# afron_atmega328_chassis_SMD.net
KiCad netlist of a schematic drawn in EAGLE
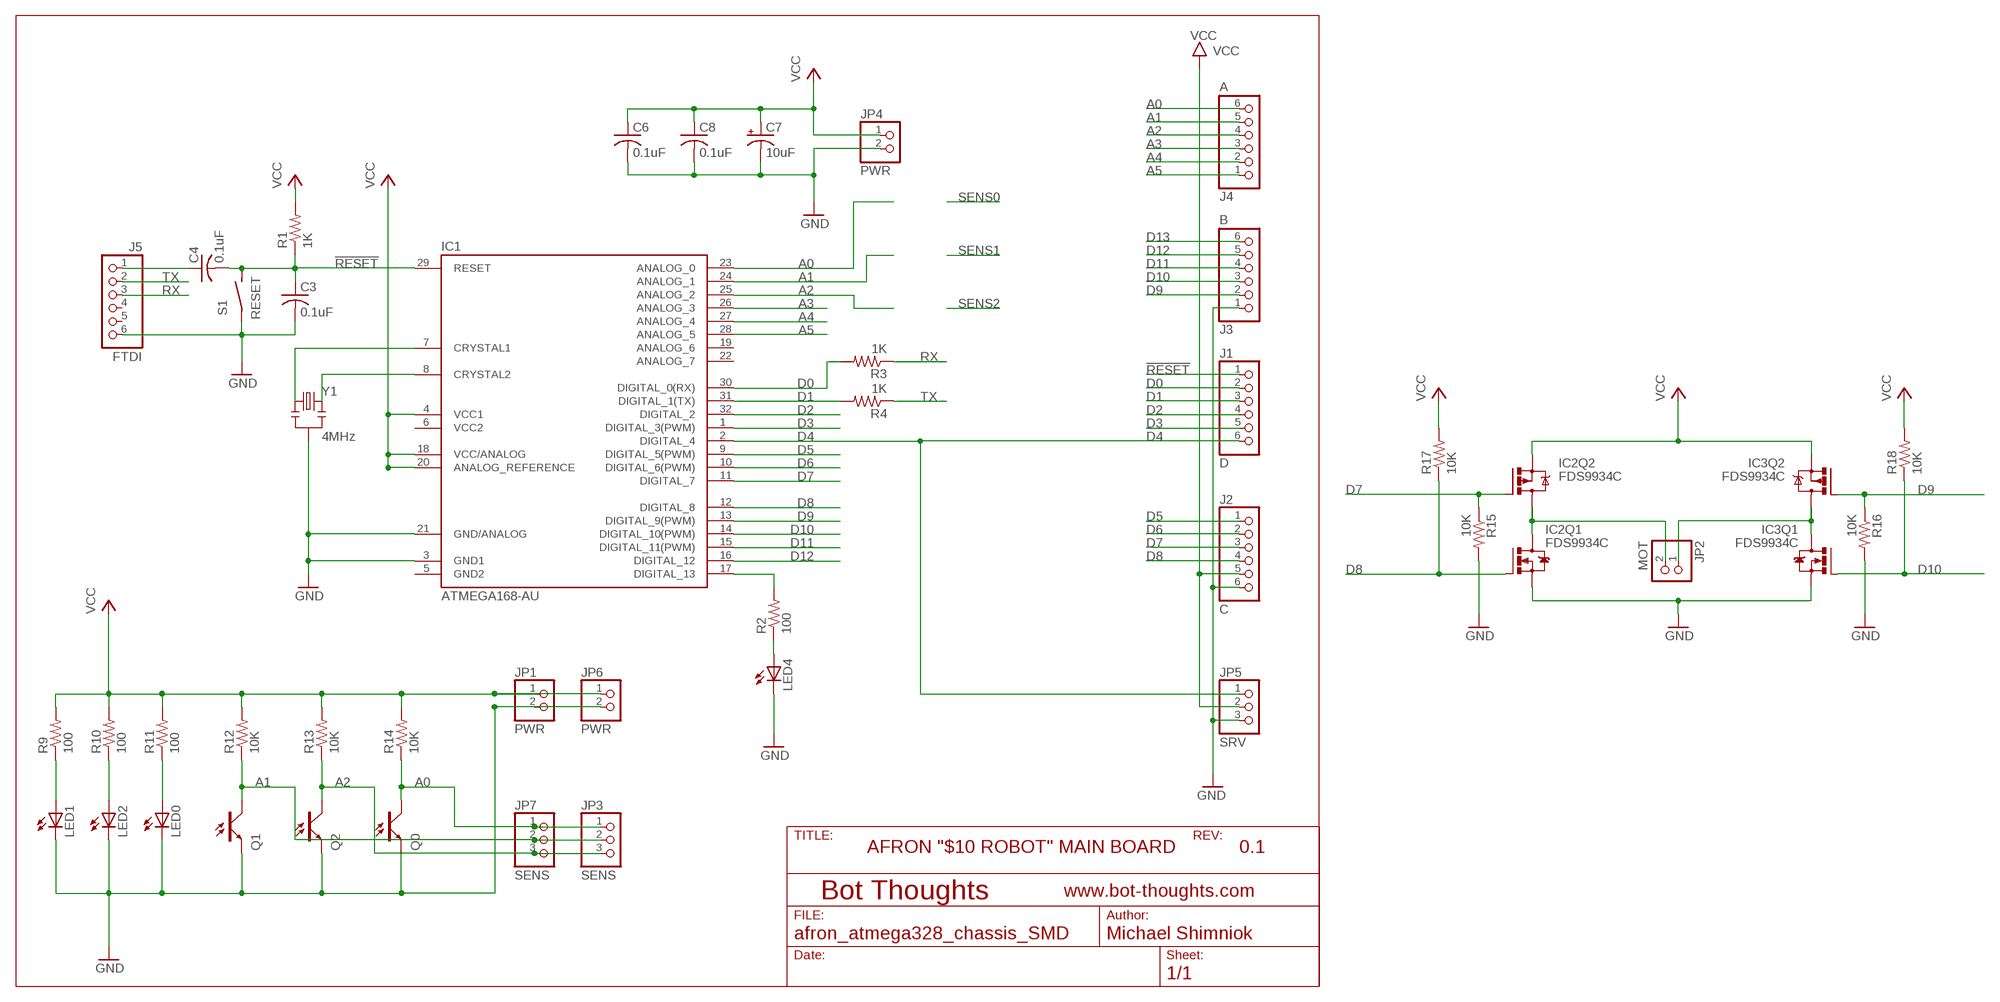
[diagram p0: schematic, sheet 1]

(export (version "E")
  (design (tool "Eeschema 10.0.6"))
  (components
    (comp (ref "C3")
      (value "0.1uF")
      (footprint "eagle-import:C0603")
      (libsource (lib "eagle-import") (part "C-USC0603"))
    )
    (comp (ref "C4")
      (value "0.1uF")
      (footprint "eagle-import:C0603")
      (libsource (lib "eagle-import") (part "C-USC0603"))
    )
    (comp (ref "C6")
      (value "0.1uF")
      (footprint "eagle-import:C0603")
      (libsource (lib "eagle-import") (part "C-USC0603"))
    )
    (comp (ref "C7")
      (value "10uF")
      (footprint "eagle-import:E2,5-6")
      (libsource (lib "eagle-import") (part "CPOL-USE2.5-6"))
    )
    (comp (ref "C8")
      (value "0.1uF")
      (footprint "eagle-import:C0603")
      (libsource (lib "eagle-import") (part "C-USC0603"))
    )
    (comp (ref "IC1")
      (value "ATMEGA168-AU")
      (footprint "eagle-import:TQFP32-08")
      (libsource (lib "eagle-import") (part "ATMEGA168-AU"))
    )
    (comp (ref "IC2")
      (value "FDS9934C")
      (footprint "eagle-import:SOIC8")
      (libsource (lib "eagle-import") (part "FDS9934C"))
    )
    (comp (ref "IC3")
      (value "FDS9934C")
      (footprint "eagle-import:SOIC8")
      (libsource (lib "eagle-import") (part "FDS9934C"))
    )
    (comp (ref "J1")
      (value "D")
      (footprint "eagle-import:1X06-S")
      (libsource (lib "eagle-import") (part "PINHD-1X06_2.54-S"))
    )
    (comp (ref "J2")
      (value "C")
      (footprint "eagle-import:1X06-S")
      (libsource (lib "eagle-import") (part "PINHD-1X06_2.54-S"))
    )
    (comp (ref "J3")
      (value "B")
      (footprint "eagle-import:1X06-S")
      (libsource (lib "eagle-import") (part "PINHD-1X06_2.54-S"))
    )
    (comp (ref "J4")
      (value "A")
      (footprint "eagle-import:1X06-S")
      (libsource (lib "eagle-import") (part "PINHD-1X06_2.54-S"))
    )
    (comp (ref "J5")
      (value "FTDI")
      (footprint "eagle-import:1X06-S")
      (libsource (lib "eagle-import") (part "PINHD-1X06_2.54-S"))
    )
    (comp (ref "JP1")
      (value "PWR")
      (footprint "eagle-import:1X02-S")
      (libsource (lib "eagle-import") (part "PINHD-1X02_2.54-S"))
    )
    (comp (ref "JP2")
      (value "MOT")
      (footprint "eagle-import:1X02-S")
      (libsource (lib "eagle-import") (part "PINHD-1X02_2.54-S"))
    )
    (comp (ref "JP3")
      (value "SENS")
      (footprint "eagle-import:1X03-S")
      (libsource (lib "eagle-import") (part "PINHD-1X03_2.54-S"))
    )
    (comp (ref "JP4")
      (value "PWR")
      (footprint "eagle-import:1X02-S")
      (libsource (lib "eagle-import") (part "PINHD-1X02_2.54-S"))
    )
    (comp (ref "JP5")
      (value "SRV")
      (footprint "eagle-import:1X03-S")
      (libsource (lib "eagle-import") (part "PINHD-1X03_2.54-S"))
    )
    (comp (ref "JP6")
      (value "PWR")
      (footprint "eagle-import:1X02-S")
      (libsource (lib "eagle-import") (part "PINHD-1X02_2.54-S"))
    )
    (comp (ref "JP7")
      (value "SENS")
      (footprint "eagle-import:1X03-S")
      (libsource (lib "eagle-import") (part "PINHD-1X03_2.54-S"))
    )
    (comp (ref "LED0")
      (value "LED3MM")
      (footprint "eagle-import:LED3MM")
      (libsource (lib "eagle-import") (part "LED3MM"))
    )
    (comp (ref "LED1")
      (value "LED3MM")
      (footprint "eagle-import:LED3MM")
      (libsource (lib "eagle-import") (part "LED3MM"))
    )
    (comp (ref "LED2")
      (value "LED3MM")
      (footprint "eagle-import:LED3MM")
      (libsource (lib "eagle-import") (part "LED3MM"))
    )
    (comp (ref "LED4")
      (value "LEDCHIP-LED0603")
      (footprint "eagle-import:CHIP-LED0603")
      (libsource (lib "eagle-import") (part "LEDCHIP-LED0603"))
    )
    (comp (ref "Q0")
      (value "PHOTOTRANSISTOR3MM")
      (footprint "eagle-import:LED3MM")
      (libsource (lib "eagle-import") (part "PHOTOTRANSISTOR3MM"))
    )
    (comp (ref "Q1")
      (value "PHOTOTRANSISTOR3MM")
      (footprint "eagle-import:LED3MM")
      (libsource (lib "eagle-import") (part "PHOTOTRANSISTOR3MM"))
    )
    (comp (ref "Q2")
      (value "PHOTOTRANSISTOR3MM")
      (footprint "eagle-import:LED3MM")
      (libsource (lib "eagle-import") (part "PHOTOTRANSISTOR3MM"))
    )
    (comp (ref "R1")
      (value "1K")
      (footprint "eagle-import:R0603")
      (libsource (lib "eagle-import") (part "R-US_R0603"))
    )
    (comp (ref "R2")
      (value "100")
      (footprint "eagle-import:R0603")
      (libsource (lib "eagle-import") (part "R-US_R0603"))
    )
    (comp (ref "R3")
      (value "1K")
      (footprint "eagle-import:R0603")
      (libsource (lib "eagle-import") (part "R-US_R0603"))
    )
    (comp (ref "R4")
      (value "1K")
      (footprint "eagle-import:R0603")
      (libsource (lib "eagle-import") (part "R-US_R0603"))
    )
    (comp (ref "R9")
      (value "100")
      (footprint "eagle-import:R0603")
      (libsource (lib "eagle-import") (part "R-US_R0603"))
    )
    (comp (ref "R10")
      (value "100")
      (footprint "eagle-import:R0603")
      (libsource (lib "eagle-import") (part "R-US_R0603"))
    )
    (comp (ref "R11")
      (value "100")
      (footprint "eagle-import:R0603")
      (libsource (lib "eagle-import") (part "R-US_R0603"))
    )
    (comp (ref "R12")
      (value "10K")
      (footprint "eagle-import:R0603")
      (libsource (lib "eagle-import") (part "R-US_R0603"))
    )
    (comp (ref "R13")
      (value "10K")
      (footprint "eagle-import:R0603")
      (libsource (lib "eagle-import") (part "R-US_R0603"))
    )
    (comp (ref "R14")
      (value "10K")
      (footprint "eagle-import:R0603")
      (libsource (lib "eagle-import") (part "R-US_R0603"))
    )
    (comp (ref "R15")
      (value "10K")
      (footprint "eagle-import:R0603")
      (libsource (lib "eagle-import") (part "R-US_R0603"))
    )
    (comp (ref "R16")
      (value "10K")
      (footprint "eagle-import:R0603")
      (libsource (lib "eagle-import") (part "R-US_R0603"))
    )
    (comp (ref "R17")
      (value "10K")
      (footprint "eagle-import:R0603")
      (libsource (lib "eagle-import") (part "R-US_R0603"))
    )
    (comp (ref "R18")
      (value "10K")
      (footprint "eagle-import:R0603")
      (libsource (lib "eagle-import") (part "R-US_R0603"))
    )
    (comp (ref "S1")
      (value "RESET")
      (footprint "eagle-import:6MMTACTTILE_RECT_SMD")
      (libsource (lib "eagle-import") (part "SPST_TACT_RECT_SMD"))
    )
    (comp (ref "Y1")
      (value "4MHz")
      (footprint "eagle-import:RESONATOR-SMD")
      (libsource (lib "eagle-import") (part "RESONATORSMD"))
    )
  )
  (nets
    (net (code "1") (name "/A0") (class "Default")
      (node (ref "IC1") (pin "23") (pinfunction "ANALOG_0_23") (pintype "bidirectional"))
      (node (ref "J4") (pin "6") (pinfunction "6_6") (pintype "passive"))
      (node (ref "JP3") (pin "1") (pinfunction "1_1") (pintype "passive"))
      (node (ref "JP7") (pin "1") (pinfunction "1_1") (pintype "passive"))
      (node (ref "Q0") (pin "A") (pinfunction "A_A") (pintype "passive"))
      (node (ref "R14") (pin "1") (pinfunction "1_1") (pintype "passive"))
    )
    (net (code "2") (name "/A1") (class "Default")
      (node (ref "IC1") (pin "24") (pinfunction "ANALOG_1_24") (pintype "bidirectional"))
      (node (ref "J4") (pin "5") (pinfunction "5_5") (pintype "passive"))
      (node (ref "JP3") (pin "2") (pinfunction "2_2") (pintype "passive"))
      (node (ref "JP7") (pin "2") (pinfunction "2_2") (pintype "passive"))
      (node (ref "Q1") (pin "A") (pinfunction "A_A") (pintype "passive"))
      (node (ref "R12") (pin "1") (pinfunction "1_1") (pintype "passive"))
    )
    (net (code "3") (name "/A2") (class "Default")
      (node (ref "IC1") (pin "25") (pinfunction "ANALOG_2_25") (pintype "bidirectional"))
      (node (ref "J4") (pin "4") (pinfunction "4_4") (pintype "passive"))
      (node (ref "JP3") (pin "3") (pinfunction "3_3") (pintype "passive"))
      (node (ref "JP7") (pin "3") (pinfunction "3_3") (pintype "passive"))
      (node (ref "Q2") (pin "A") (pinfunction "A_A") (pintype "passive"))
      (node (ref "R13") (pin "1") (pinfunction "1_1") (pintype "passive"))
    )
    (net (code "4") (name "/A3") (class "Default")
      (node (ref "IC1") (pin "26") (pinfunction "ANALOG_3_26") (pintype "bidirectional"))
      (node (ref "J4") (pin "3") (pinfunction "3_3") (pintype "passive"))
    )
    (net (code "5") (name "/A4") (class "Default")
      (node (ref "IC1") (pin "27") (pinfunction "ANALOG_4_27") (pintype "bidirectional"))
      (node (ref "J4") (pin "2") (pinfunction "2_2") (pintype "passive"))
    )
    (net (code "6") (name "/A5") (class "Default")
      (node (ref "IC1") (pin "28") (pinfunction "ANALOG_5_28") (pintype "bidirectional"))
      (node (ref "J4") (pin "1") (pinfunction "1_1") (pintype "passive"))
    )
    (net (code "7") (name "/D0") (class "Default")
      (node (ref "IC1") (pin "30") (pinfunction "DIGITAL_0(RX)_30") (pintype "bidirectional"))
      (node (ref "J1") (pin "2") (pinfunction "2_2") (pintype "passive"))
      (node (ref "R3") (pin "2") (pinfunction "2_2") (pintype "passive"))
    )
    (net (code "8") (name "/D1") (class "Default")
      (node (ref "IC1") (pin "31") (pinfunction "DIGITAL_1(TX)_31") (pintype "bidirectional"))
      (node (ref "J1") (pin "3") (pinfunction "3_3") (pintype "passive"))
      (node (ref "R4") (pin "2") (pinfunction "2_2") (pintype "passive"))
    )
    (net (code "9") (name "/D2") (class "Default")
      (node (ref "IC1") (pin "32") (pinfunction "DIGITAL_2_32") (pintype "bidirectional"))
      (node (ref "J1") (pin "4") (pinfunction "4_4") (pintype "passive"))
    )
    (net (code "10") (name "/D3") (class "Default")
      (node (ref "IC1") (pin "1") (pinfunction "DIGITAL_3(PWM)_1") (pintype "bidirectional"))
      (node (ref "J1") (pin "5") (pinfunction "5_5") (pintype "passive"))
    )
    (net (code "11") (name "/D4") (class "Default")
      (node (ref "IC1") (pin "2") (pinfunction "DIGITAL_4_2") (pintype "bidirectional"))
      (node (ref "J1") (pin "6") (pinfunction "6_6") (pintype "passive"))
      (node (ref "JP5") (pin "1") (pinfunction "1_1") (pintype "passive"))
    )
    (net (code "12") (name "/D5") (class "Default")
      (node (ref "IC1") (pin "9") (pinfunction "DIGITAL_5(PWM)_9") (pintype "bidirectional"))
      (node (ref "J2") (pin "1") (pinfunction "1_1") (pintype "passive"))
    )
    (net (code "13") (name "/D6") (class "Default")
      (node (ref "IC1") (pin "10") (pinfunction "DIGITAL_6(PWM)_10") (pintype "bidirectional"))
      (node (ref "J2") (pin "2") (pinfunction "2_2") (pintype "passive"))
    )
    (net (code "14") (name "/D7") (class "Default")
      (node (ref "IC1") (pin "11") (pinfunction "DIGITAL_7_11") (pintype "bidirectional"))
      (node (ref "IC2") (pin "4") (pinfunction "G_4") (pintype "passive"))
      (node (ref "J2") (pin "3") (pinfunction "3_3") (pintype "passive"))
      (node (ref "R15") (pin "1") (pinfunction "1_1") (pintype "passive"))
    )
    (net (code "15") (name "/D8") (class "Default")
      (node (ref "IC1") (pin "12") (pinfunction "DIGITAL_8_12") (pintype "bidirectional"))
      (node (ref "IC2") (pin "2") (pinfunction "G_2") (pintype "passive"))
      (node (ref "J2") (pin "4") (pinfunction "4_4") (pintype "passive"))
      (node (ref "R17") (pin "1") (pinfunction "1_1") (pintype "passive"))
    )
    (net (code "16") (name "/D9") (class "Default")
      (node (ref "IC1") (pin "13") (pinfunction "DIGITAL_9(PWM)_13") (pintype "bidirectional"))
      (node (ref "IC3") (pin "4") (pinfunction "G_4") (pintype "passive"))
      (node (ref "J3") (pin "2") (pinfunction "2_2") (pintype "passive"))
      (node (ref "R16") (pin "1") (pinfunction "1_1") (pintype "passive"))
    )
    (net (code "17") (name "/D10") (class "Default")
      (node (ref "IC1") (pin "14") (pinfunction "DIGITAL_10(PWM)_14") (pintype "bidirectional"))
      (node (ref "IC3") (pin "2") (pinfunction "G_2") (pintype "passive"))
      (node (ref "J3") (pin "3") (pinfunction "3_3") (pintype "passive"))
      (node (ref "R18") (pin "1") (pinfunction "1_1") (pintype "passive"))
    )
    (net (code "18") (name "/D11") (class "Default")
      (node (ref "IC1") (pin "15") (pinfunction "DIGITAL_11(PWM)_15") (pintype "bidirectional"))
      (node (ref "J3") (pin "4") (pinfunction "4_4") (pintype "passive"))
    )
    (net (code "19") (name "/D12") (class "Default")
      (node (ref "IC1") (pin "16") (pinfunction "DIGITAL_12_16") (pintype "bidirectional"))
      (node (ref "J3") (pin "5") (pinfunction "5_5") (pintype "passive"))
    )
    (net (code "20") (name "/D13") (class "Default")
      (node (ref "IC1") (pin "17") (pinfunction "DIGITAL_13_17") (pintype "bidirectional"))
      (node (ref "J3") (pin "6") (pinfunction "6_6") (pintype "passive"))
      (node (ref "R2") (pin "2") (pinfunction "2_2") (pintype "passive"))
    )
    (net (code "21") (name "/GND2") (class "Default")
      (node (ref "IC1") (pin "5") (pinfunction "GND2_5") (pintype "power_in"))
    )
    (net (code "22") (name "/RX") (class "Default")
      (node (ref "J5") (pin "3") (pinfunction "3_3") (pintype "passive"))
      (node (ref "R3") (pin "1") (pinfunction "1_1") (pintype "passive"))
    )
    (net (code "26") (name "/TX") (class "Default")
      (node (ref "J5") (pin "2") (pinfunction "2_2") (pintype "passive"))
      (node (ref "R4") (pin "1") (pinfunction "1_1") (pintype "passive"))
    )
    (net (code "27") (name "/VCC2") (class "Default")
      (node (ref "IC1") (pin "6") (pinfunction "VCC2_6") (pintype "power_in"))
    )
    (net (code "28") (name "/~{RESET}") (class "Default")
      (node (ref "C3") (pin "1") (pinfunction "1_1") (pintype "passive"))
      (node (ref "C4") (pin "2") (pinfunction "2_2") (pintype "passive"))
      (node (ref "IC1") (pin "29") (pinfunction "RESET_29") (pintype "bidirectional"))
      (node (ref "J1") (pin "1") (pinfunction "1_1") (pintype "passive"))
      (node (ref "R1") (pin "1") (pinfunction "1_1") (pintype "passive"))
      (node (ref "S1") (pin "P$2") (pinfunction "S_P$2") (pintype "passive"))
    )
    (net (code "29") (name "GND") (class "Default")
      (node (ref "C3") (pin "2") (pinfunction "2_2") (pintype "passive"))
      (node (ref "C6") (pin "2") (pinfunction "2_2") (pintype "passive"))
      (node (ref "C7") (pin "-") (pinfunction "-_-") (pintype "passive"))
      (node (ref "C8") (pin "2") (pinfunction "2_2") (pintype "passive"))
      (node (ref "IC1") (pin "21") (pinfunction "GND/ANALOG_21") (pintype "power_in"))
      (node (ref "IC1") (pin "3") (pinfunction "GND1_3") (pintype "power_in"))
      (node (ref "IC2") (pin "1") (pinfunction "S_1") (pintype "passive"))
      (node (ref "IC3") (pin "1") (pinfunction "S_1") (pintype "passive"))
      (node (ref "J2") (pin "6") (pinfunction "6_6") (pintype "passive"))
      (node (ref "J3") (pin "1") (pinfunction "1_1") (pintype "passive"))
      (node (ref "J5") (pin "6") (pinfunction "6_6") (pintype "passive"))
      (node (ref "JP1") (pin "2") (pinfunction "2_2") (pintype "passive"))
      (node (ref "JP4") (pin "2") (pinfunction "2_2") (pintype "passive"))
      (node (ref "JP5") (pin "3") (pinfunction "3_3") (pintype "passive"))
      (node (ref "JP6") (pin "2") (pinfunction "2_2") (pintype "passive"))
      (node (ref "LED0") (pin "K") (pinfunction "C_K") (pintype "passive"))
      (node (ref "LED1") (pin "K") (pinfunction "C_K") (pintype "passive"))
      (node (ref "LED2") (pin "K") (pinfunction "C_K") (pintype "passive"))
      (node (ref "LED4") (pin "C") (pinfunction "C_C") (pintype "passive"))
      (node (ref "Q0") (pin "K") (pinfunction "C_K") (pintype "passive"))
      (node (ref "Q1") (pin "K") (pinfunction "C_K") (pintype "passive"))
      (node (ref "Q2") (pin "K") (pinfunction "C_K") (pintype "passive"))
      (node (ref "R15") (pin "2") (pinfunction "2_2") (pintype "passive"))
      (node (ref "R16") (pin "2") (pinfunction "2_2") (pintype "passive"))
      (node (ref "S1") (pin "P$1") (pinfunction "P_P$1") (pintype "passive"))
      (node (ref "Y1") (pin "2") (pinfunction "2_2") (pintype "passive"))
    )
    (net (code "30") (name "Net-(C4-Pad1)") (class "Default")
      (node (ref "C4") (pin "1") (pinfunction "1_1") (pintype "passive"))
      (node (ref "J5") (pin "1") (pinfunction "1_1") (pintype "passive"))
    )
    (net (code "31") (name "Net-(IC1-CRYSTAL1)") (class "Default")
      (node (ref "IC1") (pin "7") (pinfunction "CRYSTAL1_7") (pintype "bidirectional"))
      (node (ref "Y1") (pin "1") (pinfunction "1_1") (pintype "passive"))
    )
    (net (code "32") (name "Net-(IC1-CRYSTAL2)") (class "Default")
      (node (ref "IC1") (pin "8") (pinfunction "CRYSTAL2_8") (pintype "bidirectional"))
      (node (ref "Y1") (pin "3") (pinfunction "3_3") (pintype "passive"))
    )
    (net (code "33") (name "Net-(IC2A-D-Pad7)") (class "Default")
      (node (ref "IC2") (pin "5") (pinfunction "D_5") (pintype "passive"))
      (node (ref "IC2") (pin "6") (pinfunction "D_6") (pintype "passive"))
      (node (ref "IC2") (pin "7") (pinfunction "D_7") (pintype "passive"))
      (node (ref "IC2") (pin "8") (pinfunction "D_8") (pintype "passive"))
      (node (ref "JP2") (pin "2") (pinfunction "2_2") (pintype "passive"))
    )
    (net (code "34") (name "Net-(IC3A-D-Pad7)") (class "Default")
      (node (ref "IC3") (pin "5") (pinfunction "D_5") (pintype "passive"))
      (node (ref "IC3") (pin "6") (pinfunction "D_6") (pintype "passive"))
      (node (ref "IC3") (pin "7") (pinfunction "D_7") (pintype "passive"))
      (node (ref "IC3") (pin "8") (pinfunction "D_8") (pintype "passive"))
      (node (ref "JP2") (pin "1") (pinfunction "1_1") (pintype "passive"))
    )
    (net (code "35") (name "Net-(LED0-PadA)") (class "Default")
      (node (ref "LED0") (pin "A") (pinfunction "A_A") (pintype "passive"))
      (node (ref "R11") (pin "1") (pinfunction "1_1") (pintype "passive"))
    )
    (net (code "36") (name "Net-(LED1-PadA)") (class "Default")
      (node (ref "LED1") (pin "A") (pinfunction "A_A") (pintype "passive"))
      (node (ref "R9") (pin "1") (pinfunction "1_1") (pintype "passive"))
    )
    (net (code "37") (name "Net-(LED2-PadA)") (class "Default")
      (node (ref "LED2") (pin "A") (pinfunction "A_A") (pintype "passive"))
      (node (ref "R10") (pin "1") (pinfunction "1_1") (pintype "passive"))
    )
    (net (code "38") (name "Net-(LED4-PadA)") (class "Default")
      (node (ref "LED4") (pin "A") (pinfunction "A_A") (pintype "passive"))
      (node (ref "R2") (pin "1") (pinfunction "1_1") (pintype "passive"))
    )
    (net (code "39") (name "VCC") (class "Default")
      (node (ref "C6") (pin "1") (pinfunction "1_1") (pintype "passive"))
      (node (ref "C7") (pin "+") (pinfunction "+_+") (pintype "passive"))
      (node (ref "C8") (pin "1") (pinfunction "1_1") (pintype "passive"))
      (node (ref "IC1") (pin "18") (pinfunction "VCC/ANALOG_18") (pintype "passive"))
      (node (ref "IC1") (pin "20") (pinfunction "ANALOG_REFERENCE_20") (pintype "passive"))
      (node (ref "IC1") (pin "4") (pinfunction "VCC1_4") (pintype "power_in"))
      (node (ref "IC2") (pin "3") (pinfunction "S_3") (pintype "passive"))
      (node (ref "IC3") (pin "3") (pinfunction "S_3") (pintype "passive"))
      (node (ref "J2") (pin "5") (pinfunction "5_5") (pintype "passive"))
      (node (ref "JP1") (pin "1") (pinfunction "1_1") (pintype "passive"))
      (node (ref "JP4") (pin "1") (pinfunction "1_1") (pintype "passive"))
      (node (ref "JP5") (pin "2") (pinfunction "2_2") (pintype "passive"))
      (node (ref "JP6") (pin "1") (pinfunction "1_1") (pintype "passive"))
      (node (ref "R1") (pin "2") (pinfunction "2_2") (pintype "passive"))
      (node (ref "R10") (pin "2") (pinfunction "2_2") (pintype "passive"))
      (node (ref "R11") (pin "2") (pinfunction "2_2") (pintype "passive"))
      (node (ref "R12") (pin "2") (pinfunction "2_2") (pintype "passive"))
      (node (ref "R13") (pin "2") (pinfunction "2_2") (pintype "passive"))
      (node (ref "R14") (pin "2") (pinfunction "2_2") (pintype "passive"))
      (node (ref "R17") (pin "2") (pinfunction "2_2") (pintype "passive"))
      (node (ref "R18") (pin "2") (pinfunction "2_2") (pintype "passive"))
      (node (ref "R9") (pin "2") (pinfunction "2_2") (pintype "passive"))
    )
    (net (code "40") (name "unconnected-(IC1-ANALOG_6-Pad19)") (class "Default")
      (node (ref "IC1") (pin "19") (pinfunction "ANALOG_6_19") (pintype "passive"))
    )
    (net (code "41") (name "unconnected-(IC1-ANALOG_7-Pad22)") (class "Default")
      (node (ref "IC1") (pin "22") (pinfunction "ANALOG_7_22") (pintype "passive"))
    )
    (net (code "42") (name "unconnected-(J5-Pad4)") (class "Default")
      (node (ref "J5") (pin "4") (pinfunction "4_4") (pintype "passive"))
    )
    (net (code "43") (name "unconnected-(J5-Pad5)") (class "Default")
      (node (ref "J5") (pin "5") (pinfunction "5_5") (pintype "passive"))
    )
  )
)
